# Octal_Flash.net
KiCad netlist of a schematic drawn in Altium Designer
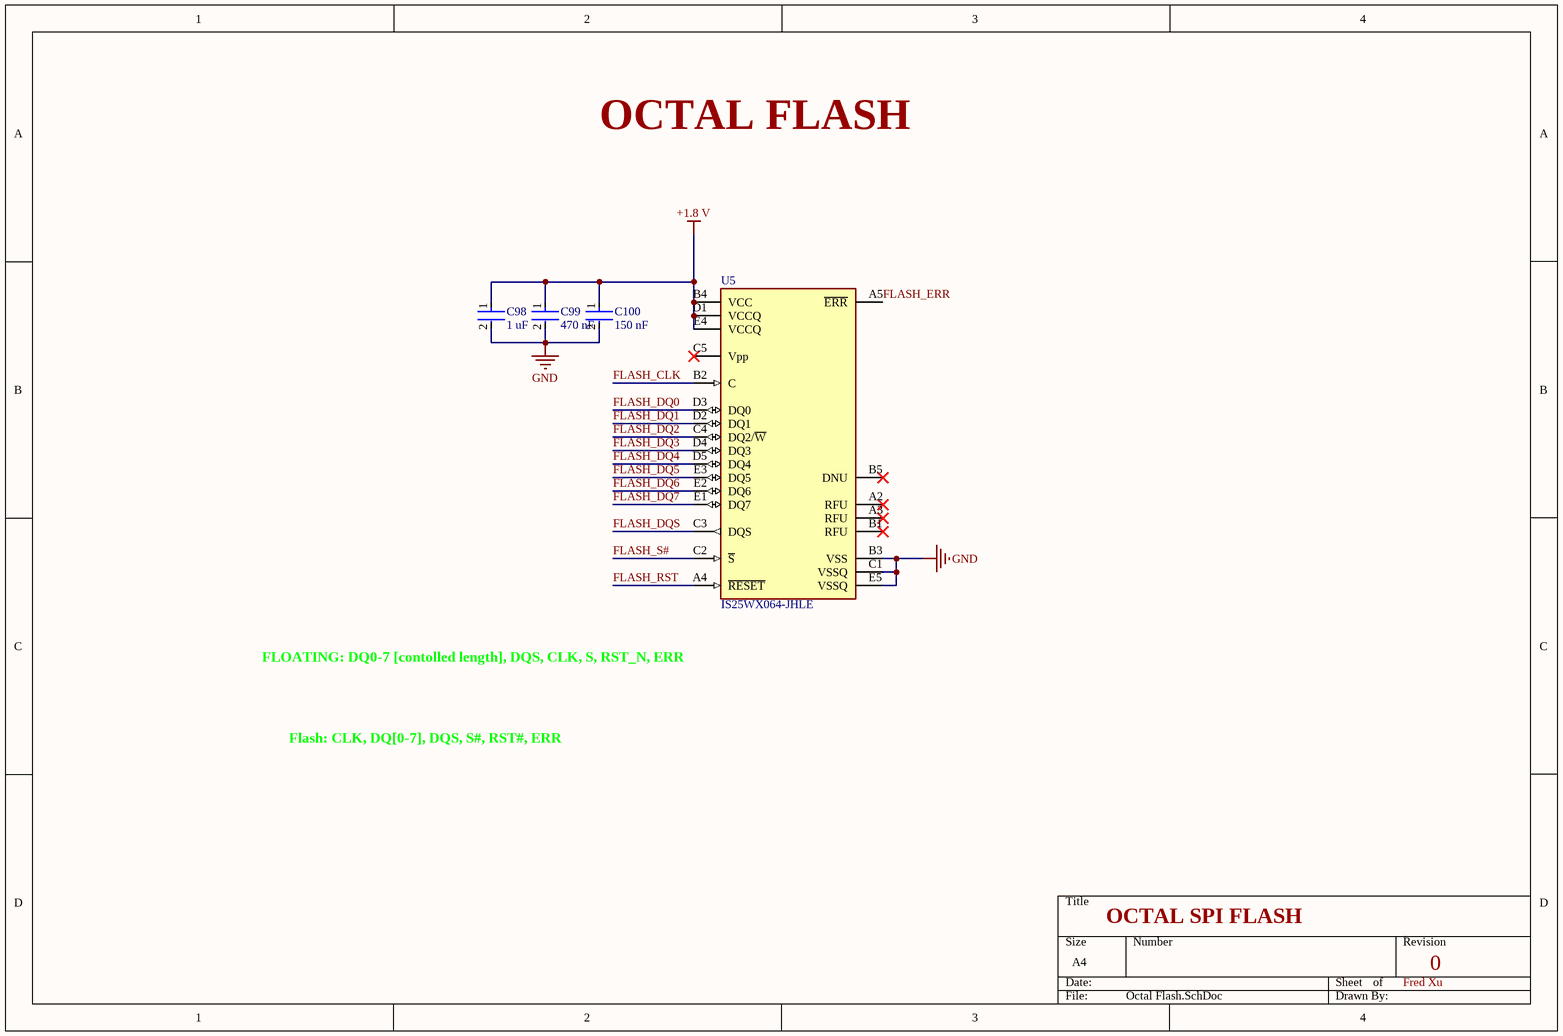
[diagram p0: Octal Flash.SchDoc]

(export (version "E")
  (design (tool "Eeschema 10.0.6"))
  (components
    (comp (ref "C98")
      (value "1 uF")
      (footprint "FP-GCM155-0_2-MFG")
      (description "Ceramic Capacitor for Automotive 1uF ±20% 10VDC X7S 0402 Paper T/R")
      (libsource (lib "Altium Content Vault") (part "11868f565c42a9108669ba33697ecf6"))
    )
    (comp (ref "C99")
      (value "470 nF")
      (footprint "FP-GRM155-0_05-IPC_B")
      (description "Chip Multilayer Ceramic Capacitors for General Purpose, 0402, 0.47uF, X7R, 15%, 20%, 10V")
      (fields (field (name "TOLERANCE") "20%"))
      (libsource (lib "Altium Content Vault") (part "02cd4be3c70576c341d710602a673aa"))
    )
    (comp (ref "C100")
      (value "150 nF")
      (footprint "FP-GCM155-0_05-MFG")
      (description "Ceramic Capacitor for Automotive 150nF ±20% 16VDC X7R 0402 Paper T/R")
      (libsource (lib "Altium Content Vault") (part "02cd4be3c70576c341d710602a673aa"))
    )
    (comp (ref "U5")
      (value "IS25WX064-JHLE")
      (footprint "FP-IS25WX064-JHLE-IPC_A")
      (description "IS25WX064-JHLE Octal Flash 64Mbit 8M X 8bit SPI 1.8V 6ns 24-Pin TFBGA")
      (libsource (lib "Altium Content Vault") (part "b0657c320c0c83de822e1c37842c9df"))
    )
  )
  (nets
    (net (code "1") (name "+1.8 V") (class "Default")
      (node (ref "C100") (pin "1") (pinfunction "1_1") (pintype "passive"))
      (node (ref "C98") (pin "1") (pinfunction "1_1") (pintype "passive"))
      (node (ref "C99") (pin "1") (pinfunction "1_1") (pintype "passive"))
      (node (ref "U5") (pin "B4") (pinfunction "VCC_B4") (pintype "power_in"))
      (node (ref "U5") (pin "D1") (pinfunction "VCCQ_D1") (pintype "power_in"))
      (node (ref "U5") (pin "E4") (pinfunction "VCCQ_E4") (pintype "power_in"))
    )
    (net (code "2") (name "/FLASH_CLK") (class "Default")
      (node (ref "U5") (pin "B2") (pinfunction "C_B2") (pintype "input"))
    )
    (net (code "3") (name "/FLASH_DQ0") (class "Default")
      (node (ref "U5") (pin "D3") (pinfunction "DQ0_D3") (pintype "bidirectional"))
    )
    (net (code "4") (name "/FLASH_DQ1") (class "Default")
      (node (ref "U5") (pin "D2") (pinfunction "DQ1_D2") (pintype "bidirectional"))
    )
    (net (code "5") (name "/FLASH_DQ2") (class "Default")
      (node (ref "U5") (pin "C4") (pinfunction "DQ2/~{W}_C4") (pintype "bidirectional"))
    )
    (net (code "6") (name "/FLASH_DQ3") (class "Default")
      (node (ref "U5") (pin "D4") (pinfunction "DQ3_D4") (pintype "bidirectional"))
    )
    (net (code "7") (name "/FLASH_DQ4") (class "Default")
      (node (ref "U5") (pin "D5") (pinfunction "DQ4_D5") (pintype "bidirectional"))
    )
    (net (code "8") (name "/FLASH_DQ5") (class "Default")
      (node (ref "U5") (pin "E3") (pinfunction "DQ5_E3") (pintype "bidirectional"))
    )
    (net (code "9") (name "/FLASH_DQ6") (class "Default")
      (node (ref "U5") (pin "E2") (pinfunction "DQ6_E2") (pintype "bidirectional"))
    )
    (net (code "10") (name "/FLASH_DQ7") (class "Default")
      (node (ref "U5") (pin "E1") (pinfunction "DQ7_E1") (pintype "bidirectional"))
    )
    (net (code "11") (name "/FLASH_DQS") (class "Default")
      (node (ref "U5") (pin "C3") (pinfunction "DQS_C3") (pintype "output"))
    )
    (net (code "12") (name "/FLASH_ERR") (class "Default")
      (node (ref "U5") (pin "A5") (pinfunction "~{ERR}_A5") (pintype "open_collector"))
    )
    (net (code "13") (name "/FLASH_RST") (class "Default")
      (node (ref "U5") (pin "A4") (pinfunction "~{RESET}_A4") (pintype "input"))
    )
    (net (code "14") (name "/FLASH_S#") (class "Default")
      (node (ref "U5") (pin "C2") (pinfunction "~{S}_C2") (pintype "input"))
    )
    (net (code "15") (name "GND") (class "Default")
      (node (ref "C100") (pin "2") (pinfunction "2_2") (pintype "passive"))
      (node (ref "C98") (pin "2") (pinfunction "2_2") (pintype "passive"))
      (node (ref "C99") (pin "2") (pinfunction "2_2") (pintype "passive"))
      (node (ref "U5") (pin "B3") (pinfunction "VSS_B3") (pintype "power_in"))
      (node (ref "U5") (pin "C1") (pinfunction "VSSQ_C1") (pintype "power_in"))
      (node (ref "U5") (pin "E5") (pinfunction "VSSQ_E5") (pintype "power_in"))
    )
    (net (code "16") (name "unconnected-(U5-DNU-PadB5)") (class "Default")
      (node (ref "U5") (pin "B5") (pinfunction "DNU_B5") (pintype "passive+no_connect"))
    )
    (net (code "17") (name "unconnected-(U5-RFU-PadA2)") (class "Default")
      (node (ref "U5") (pin "A2") (pinfunction "RFU_A2") (pintype "passive+no_connect"))
    )
    (net (code "18") (name "unconnected-(U5-RFU-PadA3)") (class "Default")
      (node (ref "U5") (pin "A3") (pinfunction "RFU_A3") (pintype "passive+no_connect"))
    )
    (net (code "19") (name "unconnected-(U5-RFU-PadB1)") (class "Default")
      (node (ref "U5") (pin "B1") (pinfunction "RFU_B1") (pintype "passive+no_connect"))
    )
    (net (code "20") (name "unconnected-(U5-Vpp-PadC5)") (class "Default")
      (node (ref "U5") (pin "C5") (pinfunction "Vpp_C5") (pintype "power_in+no_connect"))
    )
  )
)
